# 03-Accelerometer_new.net
KiCad netlist of a schematic drawn in Altium Designer
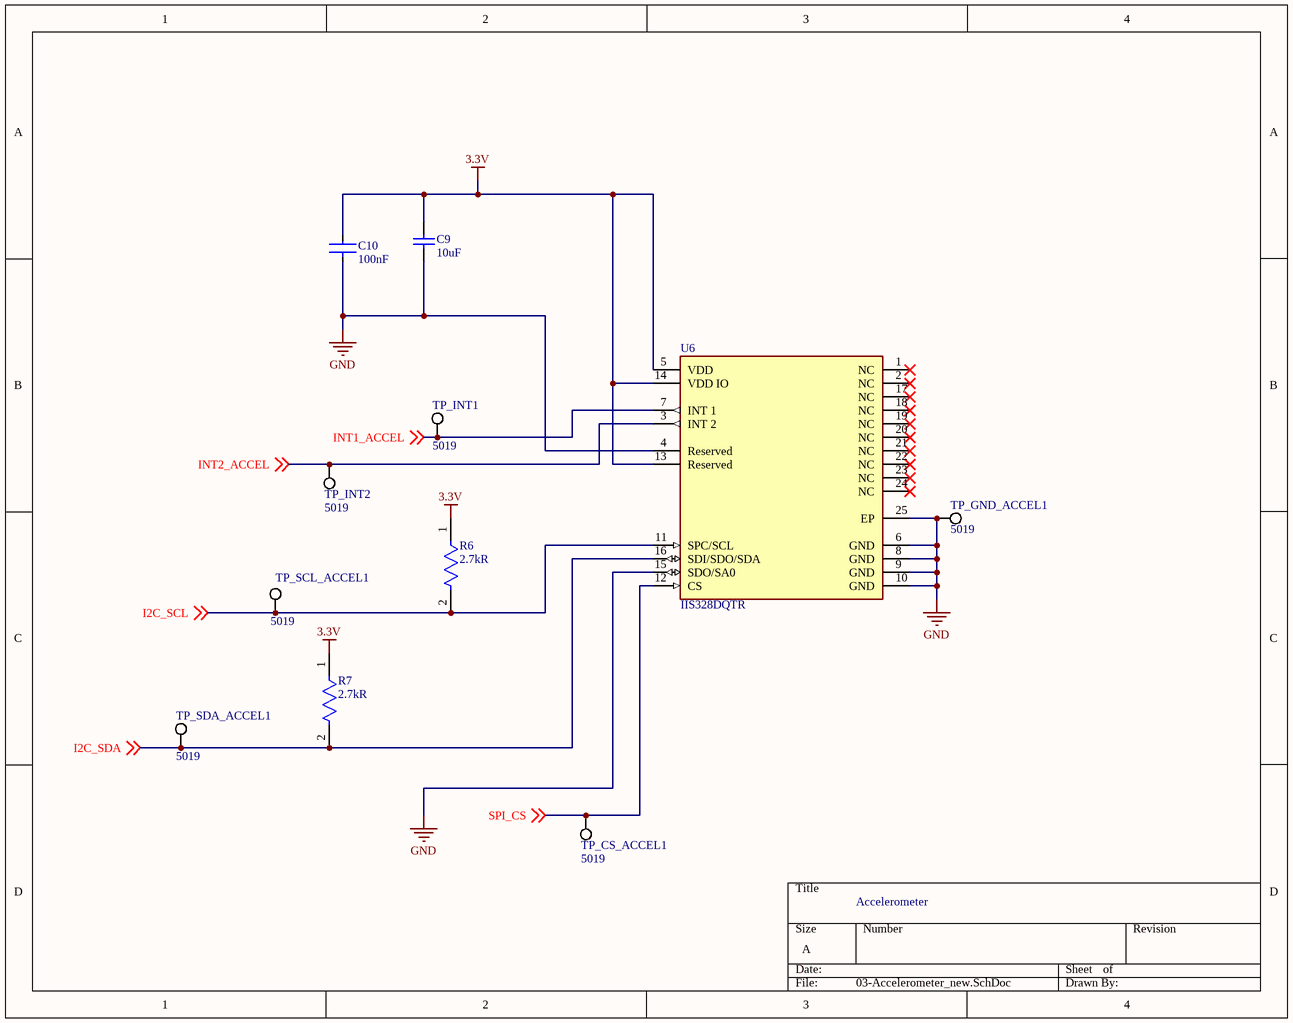
[diagram p0: 03-Accelerometer_new.SchDoc]

(export (version "E")
  (design (tool "Eeschema 10.0.6"))
  (components
    (comp (ref "C9")
      (value "TACR106M006RTA")
      (footprint "CAPC2014X150X70LL20")
      (description "10 uF Capacitor")
      (fields
        (field (name "MANUFACTURER") "AVX Interconnect / Elco")
        (field (name "CAPACITANCE") "10uF")
        (field (name "TOLERANCE") "20%")
      )
      (libsource (lib "Altium Content Vault") (part "CAP"))
    )
    (comp (ref "C10")
      (value "C2012X8R1H104K125AA")
      (footprint "FP-C2012-125-0_2-MFG")
      (description "Multilayer Ceramic Capacitors 100nF ±10% 50V X8R SMD 0805")
      (fields
        (field (name "CAPACITANCE") "100nF")
        (field (name "TOLERANCE") "10%")
        (field (name "MANUFACTURER") "TDK")
      )
      (libsource (lib "Altium Content Vault") (part "b4654b650e69147ec39a6b967a45e02"))
    )
    (comp (ref "R6")
      (value "RMCF0805JT2K70")
      (footprint "FP-RMCF0805-MFG")
      (description "2.7kΩ ±5% 0.125W 0805 Thick Film Chip Resistor AEC-Q200 compliant")
      (fields
        (field (name "RESISTANCE") "2.7kR")
        (field (name "TOLERANCE") "5%")
        (field (name "MANUFACTURER") "Stackpole Electronics")
      )
      (libsource (lib "Altium Content Vault") (part "1029c3af85768c4190bb7ad29bc67b5"))
    )
    (comp (ref "R7")
      (value "RMCF0805JT2K70")
      (footprint "FP-RMCF0805-MFG")
      (description "2.7kΩ ±5% 0.125W 0805 Thick Film Chip Resistor AEC-Q200 compliant")
      (fields
        (field (name "RESISTANCE") "2.7kR")
        (field (name "TOLERANCE") "5%")
        (field (name "MANUFACTURER") "Stackpole Electronics")
      )
      (libsource (lib "Altium Content Vault") (part "1029c3af85768c4190bb7ad29bc67b5"))
    )
    (comp (ref "TP_CS_ACCEL1")
      (value "5019")
      (footprint "KSTN-5019_V")
      (description "Test Point, 1 Position SMD, RoHS, Tape and Reel")
      (fields (field (name "MANUFACTURER") "Keystone Electronics"))
      (libsource (lib "Altium Content Vault") (part "TESTPOINT_WHITE"))
    )
    (comp (ref "TP_GND_ACCEL1")
      (value "5019")
      (footprint "KSTN-5019_V")
      (description "Test Point, 1 Position SMD, RoHS, Tape and Reel")
      (fields (field (name "MANUFACTURER") "Keystone Electronics"))
      (libsource (lib "Altium Content Vault") (part "TESTPOINT_WHITE"))
    )
    (comp (ref "TP_INT1")
      (value "5019")
      (footprint "KSTN-5019_V")
      (description "Test Point, 1 Position SMD, RoHS, Tape and Reel")
      (fields (field (name "MANUFACTURER") "Keystone Electronics"))
      (libsource (lib "Altium Content Vault") (part "TESTPOINT_WHITE"))
    )
    (comp (ref "TP_INT2")
      (value "5019")
      (footprint "KSTN-5019_V")
      (description "Test Point, 1 Position SMD, RoHS, Tape and Reel")
      (fields (field (name "MANUFACTURER") "Keystone Electronics"))
      (libsource (lib "Altium Content Vault") (part "TESTPOINT_WHITE"))
    )
    (comp (ref "TP_SCL_ACCEL1")
      (value "5019")
      (footprint "KSTN-5019_V")
      (description "Test Point, 1 Position SMD, RoHS, Tape and Reel")
      (fields (field (name "MANUFACTURER") "Keystone Electronics"))
      (libsource (lib "Altium Content Vault") (part "TESTPOINT_WHITE"))
    )
    (comp (ref "TP_SDA_ACCEL1")
      (value "5019")
      (footprint "KSTN-5019_V")
      (description "Test Point, 1 Position SMD, RoHS, Tape and Reel")
      (fields (field (name "MANUFACTURER") "Keystone Electronics"))
      (libsource (lib "Altium Content Vault") (part "TESTPOINT_WHITE"))
    )
    (comp (ref "U6")
      (value "IIS328DQTR")
      (footprint "FP-IIS328DQTR-MFG")
      (description "ACCELEROMETER 2-8G I2C/SPI 24QFN")
      (fields
        (field (name "OCTOPART") "https://octopart.com/iis328dqtr-stmicroelectronics-58187312")
        (field (name "MANUFACTURER") "STMicroelectronics")
      )
      (libsource (lib "Altium Content Vault") (part "d100f224d116b2168e24e5cefe3e3d5"))
    )
  )
  (nets
    (net (code "1") (name "3.3V") (class "Default")
      (node (ref "C10") (pin "2") (pinfunction "2_2") (pintype "passive"))
      (node (ref "C9") (pin "1") (pinfunction "1_1") (pintype "passive"))
      (node (ref "R6") (pin "1") (pinfunction "1_1") (pintype "passive"))
      (node (ref "R7") (pin "1") (pinfunction "1_1") (pintype "passive"))
      (node (ref "U6") (pin "13") (pinfunction "Reserved_13") (pintype "passive"))
      (node (ref "U6") (pin "14") (pinfunction "VDD_IO_14") (pintype "power_in"))
      (node (ref "U6") (pin "5") (pinfunction "VDD_5") (pintype "power_in"))
    )
    (net (code "2") (name "GND") (class "Default")
      (node (ref "C10") (pin "1") (pinfunction "1_1") (pintype "passive"))
      (node (ref "C9") (pin "2") (pinfunction "2_2") (pintype "passive"))
      (node (ref "TP_GND_ACCEL1") (pin "1") (pinfunction "1_1") (pintype "passive"))
      (node (ref "U6") (pin "10") (pinfunction "GND_10") (pintype "power_in"))
      (node (ref "U6") (pin "15") (pinfunction "SDO/SA0_15") (pintype "bidirectional"))
      (node (ref "U6") (pin "25") (pinfunction "EP_25") (pintype "power_in"))
      (node (ref "U6") (pin "4") (pinfunction "Reserved_4") (pintype "passive"))
      (node (ref "U6") (pin "6") (pinfunction "GND_6") (pintype "power_in"))
      (node (ref "U6") (pin "8") (pinfunction "GND_8") (pintype "power_in"))
      (node (ref "U6") (pin "9") (pinfunction "GND_9") (pintype "power_in"))
    )
    (net (code "3") (name "I2C_SCL") (class "Default")
      (node (ref "R6") (pin "2") (pinfunction "2_2") (pintype "passive"))
      (node (ref "TP_SCL_ACCEL1") (pin "1") (pinfunction "1_1") (pintype "passive"))
      (node (ref "U6") (pin "11") (pinfunction "SPC/SCL_11") (pintype "input"))
    )
    (net (code "4") (name "I2C_SDA") (class "Default")
      (node (ref "R7") (pin "2") (pinfunction "2_2") (pintype "passive"))
      (node (ref "TP_SDA_ACCEL1") (pin "1") (pinfunction "1_1") (pintype "passive"))
      (node (ref "U6") (pin "16") (pinfunction "SDI/SDO/SDA_16") (pintype "bidirectional"))
    )
    (net (code "5") (name "INT1_ACCEL") (class "Default")
      (node (ref "TP_INT1") (pin "1") (pinfunction "1_1") (pintype "passive"))
      (node (ref "U6") (pin "7") (pinfunction "INT_1_7") (pintype "output"))
    )
    (net (code "6") (name "INT2_ACCEL") (class "Default")
      (node (ref "TP_INT2") (pin "1") (pinfunction "1_1") (pintype "passive"))
      (node (ref "U6") (pin "3") (pinfunction "INT_2_3") (pintype "output"))
    )
    (net (code "7") (name "SPI_CS") (class "Default")
      (node (ref "TP_CS_ACCEL1") (pin "1") (pinfunction "1_1") (pintype "passive"))
      (node (ref "U6") (pin "12") (pinfunction "CS_12") (pintype "input"))
    )
    (net (code "8") (name "unconnected-(U6-NC-Pad1)") (class "Default")
      (node (ref "U6") (pin "1") (pinfunction "NC_1") (pintype "passive+no_connect"))
    )
    (net (code "9") (name "unconnected-(U6-NC-Pad2)") (class "Default")
      (node (ref "U6") (pin "2") (pinfunction "NC_2") (pintype "passive+no_connect"))
    )
    (net (code "10") (name "unconnected-(U6-NC-Pad17)") (class "Default")
      (node (ref "U6") (pin "17") (pinfunction "NC_17") (pintype "passive+no_connect"))
    )
    (net (code "11") (name "unconnected-(U6-NC-Pad18)") (class "Default")
      (node (ref "U6") (pin "18") (pinfunction "NC_18") (pintype "passive+no_connect"))
    )
    (net (code "12") (name "unconnected-(U6-NC-Pad19)") (class "Default")
      (node (ref "U6") (pin "19") (pinfunction "NC_19") (pintype "passive+no_connect"))
    )
    (net (code "13") (name "unconnected-(U6-NC-Pad20)") (class "Default")
      (node (ref "U6") (pin "20") (pinfunction "NC_20") (pintype "passive+no_connect"))
    )
    (net (code "14") (name "unconnected-(U6-NC-Pad21)") (class "Default")
      (node (ref "U6") (pin "21") (pinfunction "NC_21") (pintype "passive+no_connect"))
    )
    (net (code "15") (name "unconnected-(U6-NC-Pad22)") (class "Default")
      (node (ref "U6") (pin "22") (pinfunction "NC_22") (pintype "passive+no_connect"))
    )
    (net (code "16") (name "unconnected-(U6-NC-Pad23)") (class "Default")
      (node (ref "U6") (pin "23") (pinfunction "NC_23") (pintype "passive+no_connect"))
    )
    (net (code "17") (name "unconnected-(U6-NC-Pad24)") (class "Default")
      (node (ref "U6") (pin "24") (pinfunction "NC_24") (pintype "passive+no_connect"))
    )
  )
)
